# 2_MCU.net
KiCad netlist of a schematic drawn in Altium Designer
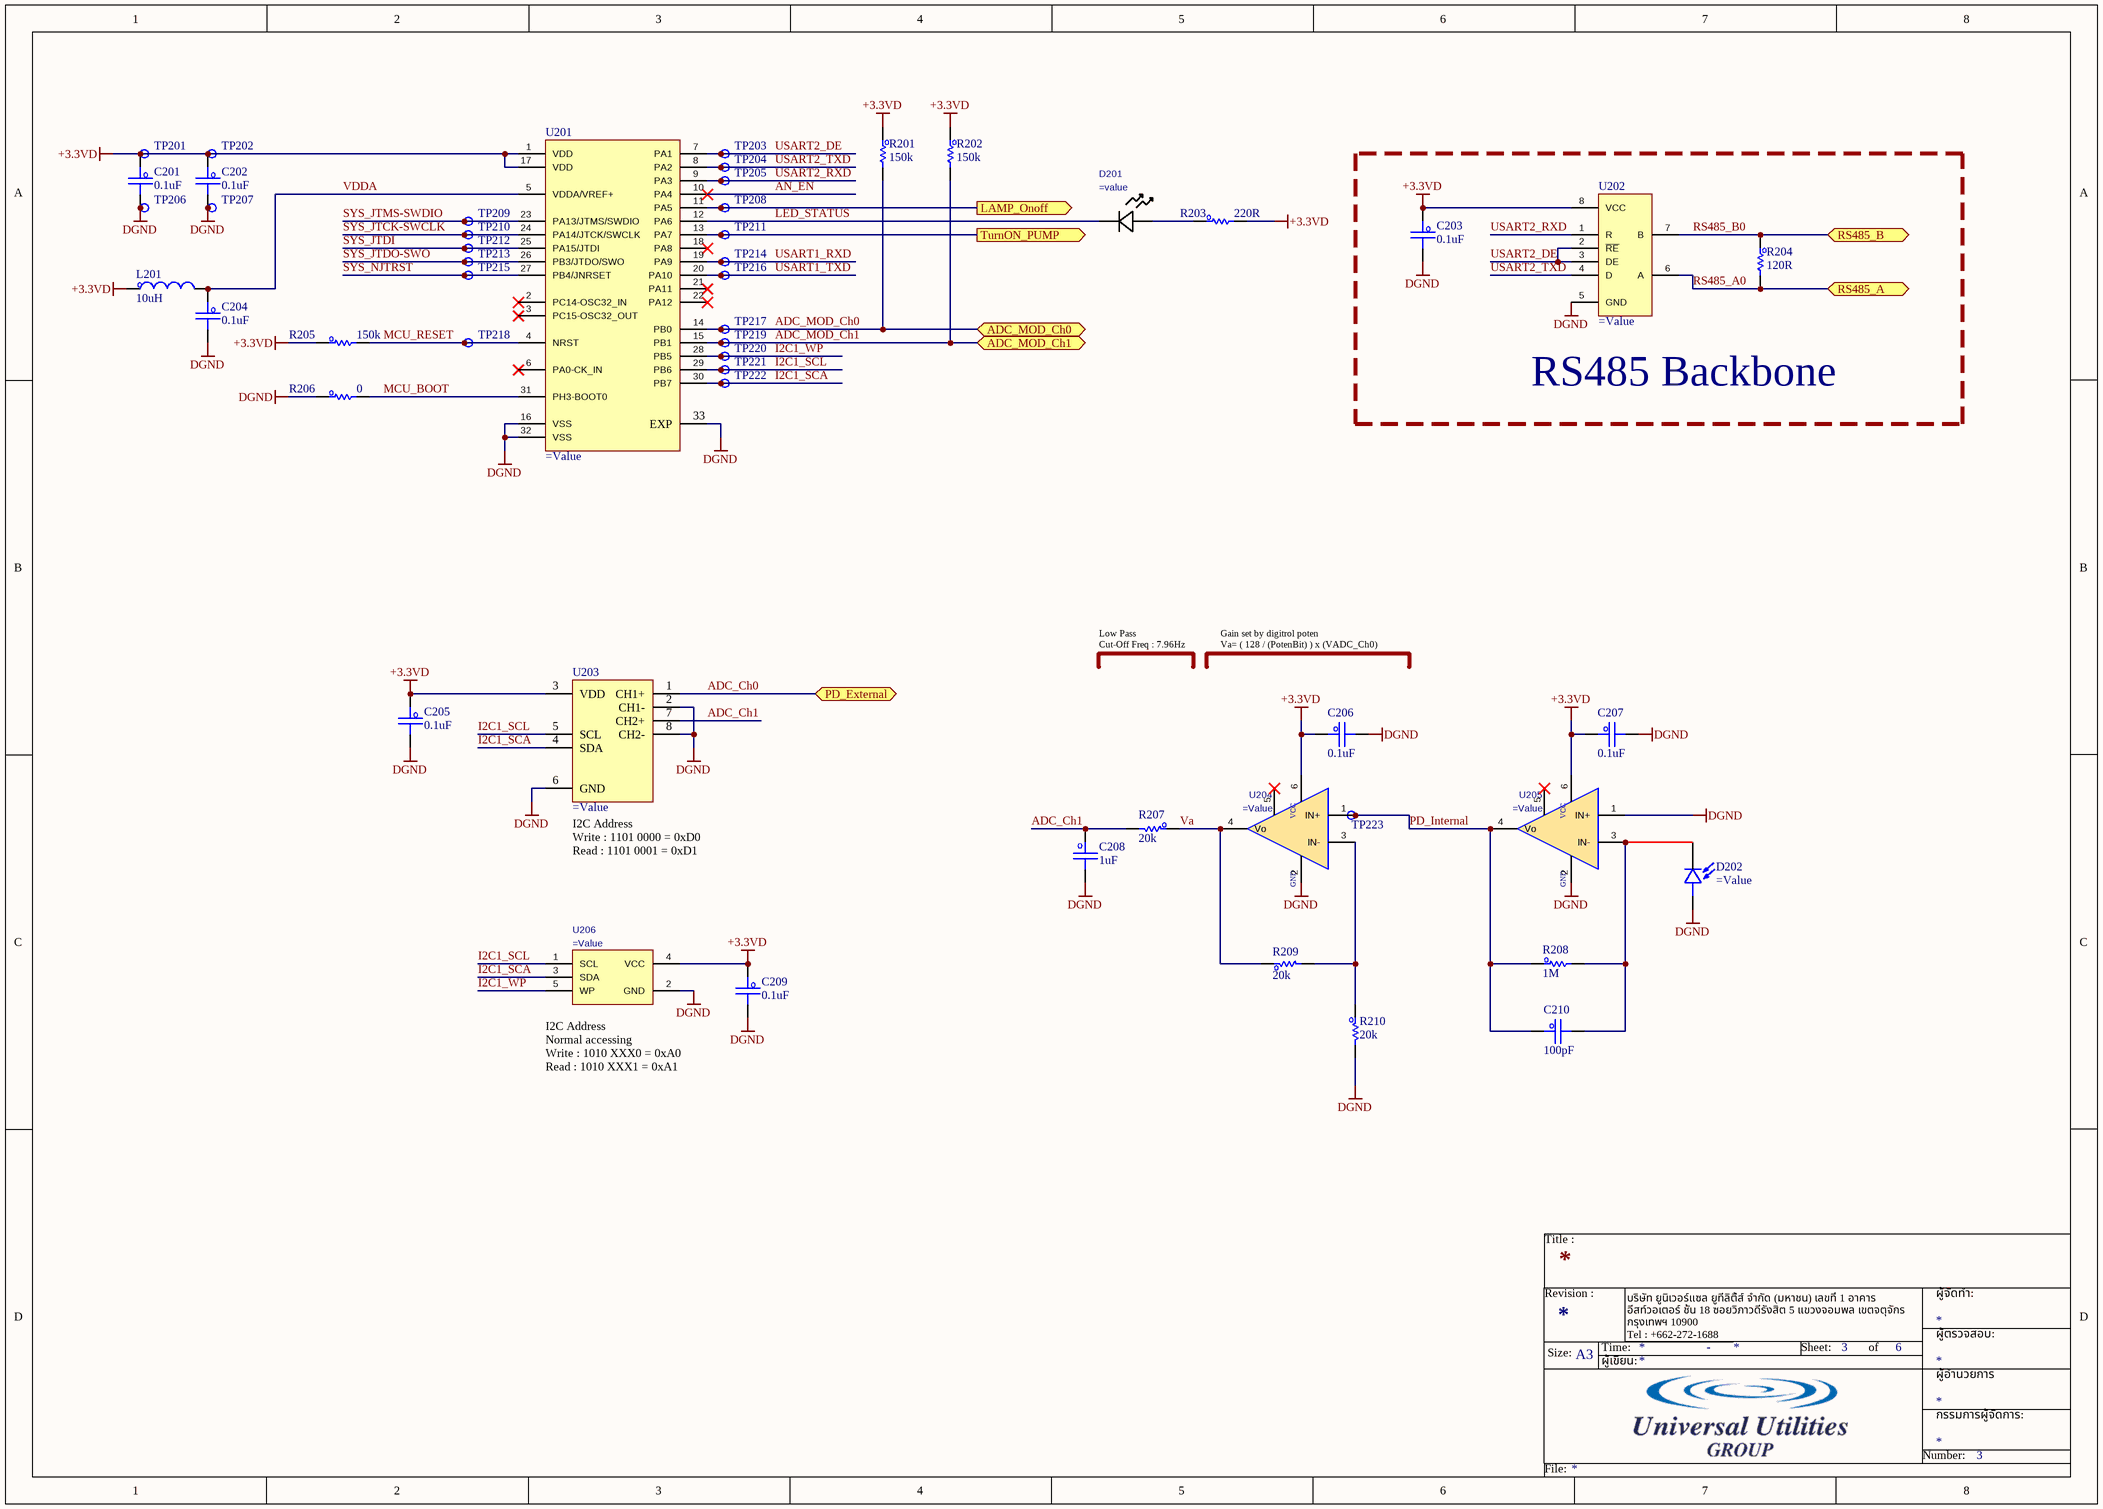
[diagram p0: 2_MCU.SchDoc]

(export (version "E")
  (design (tool "Eeschema 10.0.6"))
  (components
    (comp (ref "C201")
      (value "0.1uF")
      (footprint "C_0603")
      (description "CAP CER 0.1UF 50V X7R 0603")
      (fields (field (name "MANUFACTURER") "KEMET") (field (name "PARTNUMBER") "C0603C104K5RACTU"))
      (libsource (lib "UUSymbol") (part "C_Capacitor"))
    )
    (comp (ref "C202")
      (value "0.1uF")
      (footprint "C_0603")
      (description "CAP CER 0.1UF 50V X7R 0603")
      (fields (field (name "MANUFACTURER") "KEMET") (field (name "PARTNUMBER") "C0603C104K5RACTU"))
      (libsource (lib "UUSymbol") (part "C_Capacitor"))
    )
    (comp (ref "C203")
      (value "0.1uF")
      (footprint "C_0603")
      (description "CAP CER 0.1UF 50V X7R 0603")
      (fields (field (name "MANUFACTURER") "KEMET") (field (name "PARTNUMBER") "C0603C104K5RACTU"))
      (libsource (lib "UUSymbol") (part "C_Capacitor"))
    )
    (comp (ref "C204")
      (value "0.1uF")
      (footprint "C_0603")
      (description "CAP CER 0.1UF 50V X7R 0603")
      (fields (field (name "MANUFACTURER") "KEMET") (field (name "PARTNUMBER") "C0603C104K5RACTU"))
      (libsource (lib "UUSymbol") (part "C_Capacitor"))
    )
    (comp (ref "C205")
      (value "0.1uF")
      (footprint "C_0603")
      (description "CAP CER 0.1UF 50V X7R 0603")
      (fields (field (name "MANUFACTURER") "KEMET") (field (name "PARTNUMBER") "C0603C104K5RACTU"))
      (libsource (lib "UUSymbol") (part "C_Capacitor"))
    )
    (comp (ref "C206")
      (value "0.1uF")
      (footprint "C_0603")
      (description "CAP CER 0.1UF 50V X7R 0603")
      (fields (field (name "MANUFACTURER") "KEMET") (field (name "PARTNUMBER") "C0603C104K5RACTU"))
      (libsource (lib "UUSymbol") (part "C_Capacitor"))
    )
    (comp (ref "C207")
      (value "0.1uF")
      (footprint "C_0603")
      (description "CAP CER 0.1UF 50V X7R 0603")
      (fields (field (name "MANUFACTURER") "KEMET") (field (name "PARTNUMBER") "C0603C104K5RACTU"))
      (libsource (lib "UUSymbol") (part "C_Capacitor"))
    )
    (comp (ref "C208")
      (value "1uF")
      (footprint "C_0603")
      (description "CAP CER 0603 1UF 6.3V X7R 5%")
      (fields (field (name "MANUFACTURER") "KEMET") (field (name "PARTNUMBER") "C0603X105J9RAC7867"))
      (libsource (lib "UUSymbol") (part "C_Capacitor"))
    )
    (comp (ref "C209")
      (value "0.1uF")
      (footprint "C_0603")
      (description "CAP CER 0.1UF 50V X7R 0603")
      (fields (field (name "MANUFACTURER") "KEMET") (field (name "PARTNUMBER") "C0603C104K5RACTU"))
      (libsource (lib "UUSymbol") (part "C_Capacitor"))
    )
    (comp (ref "C210")
      (value "100pF")
      (footprint "C_0603")
      (description "CAP CER 100PF 100V X7R 0603")
      (fields (field (name "MANUFACTURER") "AVX Corporation") (field (name "PARTNUMBER") "06031C101JAT2A"))
      (libsource (lib "UUSymbol") (part "C_Capacitor"))
    )
    (comp (ref "D201")
      (value "~")
      (footprint "LED_0VS75000_WRE")
      (description "LED BLUE CLEAR 0603 SMD")
      (fields (field (name "MANUFACTURER") "Wurth Electronics") (field (name "PARTNUMBER") "150060VS75000"))
      (libsource (lib "UUSymbol") (part "D_LED_150060BS75000"))
    )
    (comp (ref "D202")
      (value "~")
      (footprint "TO254P950H570-2")
      (description "SENSOR PHOTODIODE 850NM TO39-2")
      (fields
        (field (name "PARTNUMBER") "BPX 61")
        (field (name "MANUFACTURER") "OSRAM Opto Semiconductors Inc.")
      )
      (libsource (lib "UUSymbol") (part "D_PD_BPX61"))
    )
    (comp (ref "L201")
      (value "10uH")
      (footprint "L_0402")
      (description "10µH Shielded Multilayer Inductor 250mA 1.05Ohm 0603 (1608 Metric)")
      (fields (field (name "MANUFACTURER") "TDK Corporation") (field (name "PARTNUMBER") "MLZ1608M100WT000"))
      (libsource (lib "UUSymbol") (part "L_Inductor"))
    )
    (comp (ref "R201")
      (value "150k")
      (footprint "R_0603")
      (description "RES SMD 150K OHM 1% 1/10W 0603")
      (fields (field (name "MANUFACTURER") "Vishay Dale") (field (name "PARTNUMBER") "CRCW0603150KFKEAC"))
      (libsource (lib "UUSymbol") (part "R_Resister"))
    )
    (comp (ref "R202")
      (value "150k")
      (footprint "R_0603")
      (description "RES SMD 150K OHM 1% 1/10W 0603")
      (fields (field (name "MANUFACTURER") "Vishay Dale") (field (name "PARTNUMBER") "CRCW0603150KFKEAC"))
      (libsource (lib "UUSymbol") (part "R_Resister"))
    )
    (comp (ref "R203")
      (value "220R")
      (footprint "R_0603")
      (description "RES SMD 220 OHM 1% 1/10W 0603")
      (fields (field (name "MANUFACTURER") "Vishay Dale") (field (name "PARTNUMBER") "CRCW0603220RFKEAC"))
      (libsource (lib "UUSymbol") (part "R_Resister"))
    )
    (comp (ref "R204")
      (value "120R")
      (footprint "R_0603")
      (description "RES SMD 120 OHM 1% 1/3W 0603")
      (fields (field (name "MANUFACTURER") "Vishay Dale") (field (name "PARTNUMBER") "CRCW0603120RFKEAHP"))
      (libsource (lib "UUSymbol") (part "R_Resister"))
    )
    (comp (ref "R205")
      (value "150k")
      (footprint "R_0603")
      (description "RES SMD 150K OHM 1% 1/10W 0603")
      (fields (field (name "MANUFACTURER") "Vishay Dale") (field (name "PARTNUMBER") "CRCW0603150KFKEAC"))
      (libsource (lib "UUSymbol") (part "R_Resister"))
    )
    (comp (ref "R206")
      (value "0")
      (footprint "R_0603")
      (description "RES SMD 0 OHM JUMP 1/10W 0603")
      (fields (field (name "MANUFACTURER") "Vishay Dale") (field (name "PARTNUMBER") "CRCW06030000Z0EBC"))
      (libsource (lib "UUSymbol") (part "R_Resister"))
    )
    (comp (ref "R207")
      (value "20k")
      (footprint "R_0603")
      (description "RES SMD 20K OHM 5% 1/4W 0603")
      (fields
        (field (name "MANUFACTURER") "Panasonic Electronic Components")
        (field (name "PARTNUMBER") "ERJ-PA3J203V")
      )
      (libsource (lib "UUSymbol") (part "R_Resister"))
    )
    (comp (ref "R208")
      (value "1M")
      (footprint "R_0603")
      (description "RES SMD 1M OHM 5% 1/10W 0603")
      (fields (field (name "MANUFACTURER") "YAGEO") (field (name "PARTNUMBER") "AC0603JR-071ML"))
      (libsource (lib "UUSymbol") (part "R_Resister"))
    )
    (comp (ref "R209")
      (value "20k")
      (footprint "R_0603")
      (description "RES SMD 20K OHM 5% 1/4W 0603")
      (fields
        (field (name "MANUFACTURER") "Panasonic Electronic Components")
        (field (name "PARTNUMBER") "ERJ-PA3J203V")
      )
      (libsource (lib "UUSymbol") (part "R_Resister"))
    )
    (comp (ref "R210")
      (value "20k")
      (footprint "R_0603")
      (description "RES SMD 20K OHM 5% 1/4W 0603")
      (fields
        (field (name "MANUFACTURER") "Panasonic Electronic Components")
        (field (name "PARTNUMBER") "ERJ-PA3J203V")
      )
      (libsource (lib "UUSymbol") (part "R_Resister"))
    )
    (comp (ref "TP201")
      (value "~")
      (footprint "TP_Testpoint")
      (description "TestPoint")
      (libsource (lib "UUSymbol") (part "TP_TestPoint"))
    )
    (comp (ref "TP202")
      (value "~")
      (footprint "TP_Testpoint")
      (description "TestPoint")
      (libsource (lib "UUSymbol") (part "TP_TestPoint"))
    )
    (comp (ref "TP203")
      (value "~")
      (footprint "TP_Testpoint")
      (description "TestPoint")
      (libsource (lib "UUSymbol") (part "TP_TestPoint"))
    )
    (comp (ref "TP204")
      (value "~")
      (footprint "TP_Testpoint")
      (description "TestPoint")
      (libsource (lib "UUSymbol") (part "TP_TestPoint"))
    )
    (comp (ref "TP205")
      (value "~")
      (footprint "TP_Testpoint")
      (description "TestPoint")
      (libsource (lib "UUSymbol") (part "TP_TestPoint"))
    )
    (comp (ref "TP206")
      (value "~")
      (footprint "TP_Testpoint")
      (description "TestPoint")
      (libsource (lib "UUSymbol") (part "TP_TestPoint"))
    )
    (comp (ref "TP207")
      (value "~")
      (footprint "TP_Testpoint")
      (description "TestPoint")
      (libsource (lib "UUSymbol") (part "TP_TestPoint"))
    )
    (comp (ref "TP208")
      (value "~")
      (footprint "TP_Testpoint")
      (description "TestPoint")
      (libsource (lib "UUSymbol") (part "TP_TestPoint"))
    )
    (comp (ref "TP209")
      (value "~")
      (footprint "TP_Testpoint")
      (description "TestPoint")
      (libsource (lib "UUSymbol") (part "TP_TestPoint"))
    )
    (comp (ref "TP210")
      (value "~")
      (footprint "TP_Testpoint")
      (description "TestPoint")
      (libsource (lib "UUSymbol") (part "TP_TestPoint"))
    )
    (comp (ref "TP211")
      (value "~")
      (footprint "TP_Testpoint")
      (description "TestPoint")
      (libsource (lib "UUSymbol") (part "TP_TestPoint"))
    )
    (comp (ref "TP212")
      (value "~")
      (footprint "TP_Testpoint")
      (description "TestPoint")
      (libsource (lib "UUSymbol") (part "TP_TestPoint"))
    )
    (comp (ref "TP213")
      (value "~")
      (footprint "TP_Testpoint")
      (description "TestPoint")
      (libsource (lib "UUSymbol") (part "TP_TestPoint"))
    )
    (comp (ref "TP214")
      (value "~")
      (footprint "TP_Testpoint")
      (description "TestPoint")
      (libsource (lib "UUSymbol") (part "TP_TestPoint"))
    )
    (comp (ref "TP215")
      (value "~")
      (footprint "TP_Testpoint")
      (description "TestPoint")
      (libsource (lib "UUSymbol") (part "TP_TestPoint"))
    )
    (comp (ref "TP216")
      (value "~")
      (footprint "TP_Testpoint")
      (description "TestPoint")
      (libsource (lib "UUSymbol") (part "TP_TestPoint"))
    )
    (comp (ref "TP217")
      (value "~")
      (footprint "TP_Testpoint")
      (description "TestPoint")
      (libsource (lib "UUSymbol") (part "TP_TestPoint"))
    )
    (comp (ref "TP218")
      (value "~")
      (footprint "TP_Testpoint")
      (description "TestPoint")
      (libsource (lib "UUSymbol") (part "TP_TestPoint"))
    )
    (comp (ref "TP219")
      (value "~")
      (footprint "TP_Testpoint")
      (description "TestPoint")
      (libsource (lib "UUSymbol") (part "TP_TestPoint"))
    )
    (comp (ref "TP220")
      (value "~")
      (footprint "TP_Testpoint")
      (description "TestPoint")
      (libsource (lib "UUSymbol") (part "TP_TestPoint"))
    )
    (comp (ref "TP221")
      (value "~")
      (footprint "TP_Testpoint")
      (description "TestPoint")
      (libsource (lib "UUSymbol") (part "TP_TestPoint"))
    )
    (comp (ref "TP222")
      (value "~")
      (footprint "TP_Testpoint")
      (description "TestPoint")
      (libsource (lib "UUSymbol") (part "TP_TestPoint"))
    )
    (comp (ref "TP223")
      (value "~")
      (footprint "TP_Testpoint")
      (description "TestPoint")
      (libsource (lib "UUSymbol") (part "TP_TestPoint"))
    )
    (comp (ref "U201")
      (value "~")
      (footprint "QFN50P500X500X60-33N")
      (description "IC MCU 32BIT 256KB FLSH 32UFQFPN")
      (fields (field (name "PARTNUMBER") "STM32L432KCU6") (field (name "MANUFACTURER") "STMicroelectronics"))
      (libsource (lib "UUSymbol") (part "IC_MCU_STM32L432"))
    )
    (comp (ref "U202")
      (value "~")
      (footprint "SOP65P490X110-8N")
      (description "IC TRANSCEIVER FULL 1/1 8VSSOP")
      (fields (field (name "PARTNUMBER") "SN65HVD77DGKR") (field (name "MANUFACTURER") "Texas Instruments"))
      (libsource (lib "UUSymbol") (part "IC_TRAN_SN65HVD78DGK"))
    )
    (comp (ref "U203")
      (value "~")
      (footprint "SON50P200X300X100-9N")
      (description "IC ADC 18BIT SIGMA-DELTA 8DFN")
      (fields
        (field (name "PARTNUMBER") "MCP3422A0-E/MC")
        (field (name "MANUFACTURER") "Microchip Technology")
      )
      (libsource (lib "UUSymbol") (part "IC_ADC_MCP3422A0"))
    )
    (comp (ref "U204")
      (value "~")
      (footprint "SOT65P210X110-6N")
      (description "LOW POWER, PRECISION, 50 MHZ DEC")
      (fields (field (name "MANUFACTURER") "Texas Instruments") (field (name "PARTNUMBER") "OPA607IDCKR"))
      (libsource (lib "UUSymbol") (part "IC_OPAMP_OPA607"))
    )
    (comp (ref "U205")
      (value "~")
      (footprint "SOT65P210X110-6N")
      (description "LOW POWER, PRECISION, 50 MHZ DEC")
      (fields (field (name "MANUFACTURER") "Texas Instruments") (field (name "PARTNUMBER") "OPA607IDCKR"))
      (libsource (lib "UUSymbol") (part "IC_OPAMP_OPA607"))
    )
    (comp (ref "U206")
      (value "~")
      (footprint "SOT65P210X110-5N")
      (description "IC EEPROM 2KBIT I2C SC70-5")
      (fields
        (field (name "MANUFACTURER") "Microchip Technology")
        (field (name "PARTNUMBER") "24AA02HT-I/LT")
      )
      (libsource (lib "UUSymbol") (part "IC_MEM_24AA02HT"))
    )
  )
  (nets
    (net (code "1") (name "+3.3VD") (class "Default")
      (node (ref "C201") (pin "1") (pinfunction "1_1") (pintype "passive"))
      (node (ref "C202") (pin "1") (pinfunction "1_1") (pintype "passive"))
      (node (ref "C203") (pin "1") (pinfunction "1_1") (pintype "passive"))
      (node (ref "C205") (pin "1") (pinfunction "1_1") (pintype "passive"))
      (node (ref "C206") (pin "1") (pinfunction "1_1") (pintype "passive"))
      (node (ref "C207") (pin "1") (pinfunction "1_1") (pintype "passive"))
      (node (ref "C209") (pin "1") (pinfunction "1_1") (pintype "passive"))
      (node (ref "L201") (pin "1") (pinfunction "1_1") (pintype "passive"))
      (node (ref "R201") (pin "1") (pinfunction "1_1") (pintype "passive"))
      (node (ref "R202") (pin "1") (pinfunction "1_1") (pintype "passive"))
      (node (ref "R203") (pin "2") (pinfunction "2_2") (pintype "passive"))
      (node (ref "R205") (pin "1") (pinfunction "1_1") (pintype "passive"))
      (node (ref "TP201") (pin "1") (pinfunction "1_1") (pintype "passive"))
      (node (ref "TP202") (pin "1") (pinfunction "1_1") (pintype "passive"))
      (node (ref "U201") (pin "1") (pinfunction "VDD_1") (pintype "passive"))
      (node (ref "U201") (pin "17") (pinfunction "VDD_17") (pintype "passive"))
      (node (ref "U202") (pin "8") (pinfunction "VCC_8") (pintype "passive"))
      (node (ref "U203") (pin "3") (pinfunction "VDD_3") (pintype "passive"))
      (node (ref "U204") (pin "6") (pinfunction "VDD_6") (pintype "passive"))
      (node (ref "U205") (pin "6") (pinfunction "VDD_6") (pintype "passive"))
      (node (ref "U206") (pin "4") (pinfunction "VCC_4") (pintype "passive"))
    )
    (net (code "2") (name "/ADC_Ch0") (class "Default")
      (node (ref "U203") (pin "1") (pinfunction "CH1+_1") (pintype "passive"))
    )
    (net (code "3") (name "/ADC_Ch1") (class "Default")
      (node (ref "C208") (pin "1") (pinfunction "1_1") (pintype "passive"))
      (node (ref "R207") (pin "2") (pinfunction "2_2") (pintype "passive"))
      (node (ref "U203") (pin "7") (pinfunction "CH2+_7") (pintype "passive"))
    )
    (net (code "4") (name "/ADC_MOD_Ch0") (class "Default")
      (node (ref "R201") (pin "2") (pinfunction "2_2") (pintype "passive"))
      (node (ref "TP217") (pin "1") (pinfunction "1_1") (pintype "passive"))
      (node (ref "U201") (pin "14") (pinfunction "PB0_14") (pintype "passive"))
    )
    (net (code "5") (name "/ADC_MOD_Ch1") (class "Default")
      (node (ref "R202") (pin "2") (pinfunction "2_2") (pintype "passive"))
      (node (ref "TP219") (pin "1") (pinfunction "1_1") (pintype "passive"))
      (node (ref "U201") (pin "15") (pinfunction "PB1_15") (pintype "passive"))
    )
    (net (code "6") (name "/AN_EN") (class "Default")
      (node (ref "U201") (pin "10") (pinfunction "PA4_10") (pintype "passive+no_connect"))
    )
    (net (code "7") (name "/I2C1_SCA") (class "Default")
      (node (ref "TP222") (pin "1") (pinfunction "1_1") (pintype "passive"))
      (node (ref "U201") (pin "30") (pinfunction "PB7_30") (pintype "passive"))
      (node (ref "U203") (pin "4") (pinfunction "SDA_4") (pintype "passive"))
      (node (ref "U206") (pin "3") (pinfunction "SDA_3") (pintype "passive"))
    )
    (net (code "8") (name "/I2C1_SCL") (class "Default")
      (node (ref "TP221") (pin "1") (pinfunction "1_1") (pintype "passive"))
      (node (ref "U201") (pin "29") (pinfunction "PB6_29") (pintype "passive"))
      (node (ref "U203") (pin "5") (pinfunction "SCL_5") (pintype "passive"))
      (node (ref "U206") (pin "1") (pinfunction "SCL_1") (pintype "passive"))
    )
    (net (code "9") (name "/I2C1_WP") (class "Default")
      (node (ref "TP220") (pin "1") (pinfunction "1_1") (pintype "passive"))
      (node (ref "U201") (pin "28") (pinfunction "PB5_28") (pintype "passive"))
      (node (ref "U206") (pin "5") (pinfunction "WP_5") (pintype "passive"))
    )
    (net (code "10") (name "/LAMP_Onoff") (class "Default")
      (node (ref "TP208") (pin "1") (pinfunction "1_1") (pintype "passive"))
      (node (ref "U201") (pin "11") (pinfunction "PA5_11") (pintype "passive"))
    )
    (net (code "11") (name "/LED_STATUS") (class "Default")
      (node (ref "D201") (pin "2") (pinfunction "2_2") (pintype "passive"))
      (node (ref "U201") (pin "12") (pinfunction "PA6_12") (pintype "passive"))
    )
    (net (code "12") (name "/MCU_BOOT") (class "Default")
      (node (ref "R206") (pin "2") (pinfunction "2_2") (pintype "passive"))
      (node (ref "U201") (pin "31") (pinfunction "PH3-BOOT0_31") (pintype "passive"))
    )
    (net (code "13") (name "/MCU_RESET") (class "Default")
      (node (ref "R205") (pin "2") (pinfunction "2_2") (pintype "passive"))
      (node (ref "TP218") (pin "1") (pinfunction "1_1") (pintype "passive"))
      (node (ref "U201") (pin "4") (pinfunction "NRST_4") (pintype "passive"))
    )
    (net (code "14") (name "/PD_Internal") (class "Default")
      (node (ref "C210") (pin "1") (pinfunction "1_1") (pintype "passive"))
      (node (ref "R208") (pin "1") (pinfunction "1_1") (pintype "passive"))
      (node (ref "TP223") (pin "1") (pinfunction "1_1") (pintype "passive"))
      (node (ref "U204") (pin "1") (pinfunction "IN+_1") (pintype "passive"))
      (node (ref "U205") (pin "4") (pinfunction "Vo_4") (pintype "passive"))
    )
    (net (code "15") (name "/RS485_A0") (class "Default")
      (node (ref "R204") (pin "2") (pinfunction "2_2") (pintype "passive"))
      (node (ref "U202") (pin "6") (pinfunction "A_6") (pintype "passive"))
    )
    (net (code "16") (name "/RS485_B0") (class "Default")
      (node (ref "R204") (pin "1") (pinfunction "1_1") (pintype "passive"))
      (node (ref "U202") (pin "7") (pinfunction "B_7") (pintype "passive"))
    )
    (net (code "17") (name "/SYS_JTCK-SWCLK") (class "Default")
      (node (ref "TP210") (pin "1") (pinfunction "1_1") (pintype "passive"))
      (node (ref "U201") (pin "24") (pinfunction "PA14/JTCK/SWCLK_24") (pintype "passive"))
    )
    (net (code "18") (name "/SYS_JTDI") (class "Default")
      (node (ref "TP212") (pin "1") (pinfunction "1_1") (pintype "passive"))
      (node (ref "U201") (pin "25") (pinfunction "PA15/JTDI_25") (pintype "passive"))
    )
    (net (code "19") (name "/SYS_JTDO-SWO") (class "Default")
      (node (ref "TP213") (pin "1") (pinfunction "1_1") (pintype "passive"))
      (node (ref "U201") (pin "26") (pinfunction "PB3/JTDO/SWO_26") (pintype "passive"))
    )
    (net (code "20") (name "/SYS_JTMS-SWDIO") (class "Default")
      (node (ref "TP209") (pin "1") (pinfunction "1_1") (pintype "passive"))
      (node (ref "U201") (pin "23") (pinfunction "PA13/JTMS/SWDIO_23") (pintype "passive"))
    )
    (net (code "21") (name "/SYS_NJTRST") (class "Default")
      (node (ref "TP215") (pin "1") (pinfunction "1_1") (pintype "passive"))
      (node (ref "U201") (pin "27") (pinfunction "PB4/JNRSET_27") (pintype "passive"))
    )
    (net (code "22") (name "/TurnON_PUMP") (class "Default")
      (node (ref "TP211") (pin "1") (pinfunction "1_1") (pintype "passive"))
      (node (ref "U201") (pin "13") (pinfunction "PA7_13") (pintype "passive"))
    )
    (net (code "23") (name "/USART1_RXD") (class "Default")
      (node (ref "TP214") (pin "1") (pinfunction "1_1") (pintype "passive"))
      (node (ref "U201") (pin "19") (pinfunction "PA9_19") (pintype "passive"))
    )
    (net (code "24") (name "/USART1_TXD") (class "Default")
      (node (ref "TP216") (pin "1") (pinfunction "1_1") (pintype "passive"))
      (node (ref "U201") (pin "20") (pinfunction "PA10_20") (pintype "passive"))
    )
    (net (code "25") (name "/USART2_DE") (class "Default")
      (node (ref "TP203") (pin "1") (pinfunction "1_1") (pintype "passive"))
      (node (ref "U201") (pin "7") (pinfunction "PA1_7") (pintype "passive"))
      (node (ref "U202") (pin "2") (pinfunction "~{RE}_2") (pintype "passive"))
      (node (ref "U202") (pin "3") (pinfunction "DE_3") (pintype "passive"))
    )
    (net (code "26") (name "/USART2_RXD") (class "Default")
      (node (ref "TP205") (pin "1") (pinfunction "1_1") (pintype "passive"))
      (node (ref "U201") (pin "9") (pinfunction "PA3_9") (pintype "passive"))
      (node (ref "U202") (pin "1") (pinfunction "R_1") (pintype "passive"))
    )
    (net (code "27") (name "/USART2_TXD") (class "Default")
      (node (ref "TP204") (pin "1") (pinfunction "1_1") (pintype "passive"))
      (node (ref "U201") (pin "8") (pinfunction "PA2_8") (pintype "passive"))
      (node (ref "U202") (pin "4") (pinfunction "D_4") (pintype "passive"))
    )
    (net (code "28") (name "/VDDA") (class "Default")
      (node (ref "C204") (pin "1") (pinfunction "1_1") (pintype "passive"))
      (node (ref "L201") (pin "2") (pinfunction "2_2") (pintype "passive"))
      (node (ref "U201") (pin "5") (pinfunction "VDDA/VREF+_5") (pintype "passive"))
    )
    (net (code "29") (name "/Va") (class "Default")
      (node (ref "R207") (pin "1") (pinfunction "1_1") (pintype "passive"))
      (node (ref "R209") (pin "1") (pinfunction "1_1") (pintype "passive"))
      (node (ref "U204") (pin "4") (pinfunction "Vo_4") (pintype "passive"))
    )
    (net (code "30") (name "DGND") (class "Default")
      (node (ref "C201") (pin "2") (pinfunction "2_2") (pintype "passive"))
      (node (ref "C202") (pin "2") (pinfunction "2_2") (pintype "passive"))
      (node (ref "C203") (pin "2") (pinfunction "2_2") (pintype "passive"))
      (node (ref "C204") (pin "2") (pinfunction "2_2") (pintype "passive"))
      (node (ref "C205") (pin "2") (pinfunction "2_2") (pintype "passive"))
      (node (ref "C206") (pin "2") (pinfunction "2_2") (pintype "passive"))
      (node (ref "C207") (pin "2") (pinfunction "2_2") (pintype "passive"))
      (node (ref "C208") (pin "2") (pinfunction "2_2") (pintype "passive"))
      (node (ref "C209") (pin "2") (pinfunction "2_2") (pintype "passive"))
      (node (ref "D202") (pin "A") (pinfunction "A_A") (pintype "passive"))
      (node (ref "R206") (pin "1") (pinfunction "1_1") (pintype "passive"))
      (node (ref "R210") (pin "2") (pinfunction "2_2") (pintype "passive"))
      (node (ref "TP206") (pin "1") (pinfunction "1_1") (pintype "passive"))
      (node (ref "TP207") (pin "1") (pinfunction "1_1") (pintype "passive"))
      (node (ref "U201") (pin "16") (pinfunction "VSS_16") (pintype "passive"))
      (node (ref "U201") (pin "32") (pinfunction "VSS_32") (pintype "passive"))
      (node (ref "U201") (pin "33") (pinfunction "EXP_33") (pintype "passive"))
      (node (ref "U202") (pin "5") (pinfunction "GND_5") (pintype "passive"))
      (node (ref "U203") (pin "2") (pinfunction "CH1-_2") (pintype "passive"))
      (node (ref "U203") (pin "6") (pinfunction "GND_6") (pintype "passive"))
      (node (ref "U203") (pin "8") (pinfunction "CH2-_8") (pintype "passive"))
      (node (ref "U204") (pin "2") (pinfunction "GND_2") (pintype "passive"))
      (node (ref "U205") (pin "1") (pinfunction "IN+_1") (pintype "passive"))
      (node (ref "U205") (pin "2") (pinfunction "GND_2") (pintype "passive"))
      (node (ref "U206") (pin "2") (pinfunction "GND_2") (pintype "passive"))
    )
    (net (code "31") (name "Net-(D201-Pad1)") (class "Default")
      (node (ref "D201") (pin "1") (pinfunction "1_1") (pintype "passive"))
      (node (ref "R203") (pin "1") (pinfunction "1_1") (pintype "passive"))
    )
    (net (code "32") (name "Net-(U204-IN-)") (class "Default")
      (node (ref "R209") (pin "2") (pinfunction "2_2") (pintype "passive"))
      (node (ref "R210") (pin "1") (pinfunction "1_1") (pintype "passive"))
      (node (ref "U204") (pin "3") (pinfunction "IN-_3") (pintype "passive"))
    )
    (net (code "33") (name "Net-(U205-IN-)") (class "Default")
      (node (ref "C210") (pin "2") (pinfunction "2_2") (pintype "passive"))
      (node (ref "D202") (pin "C") (pinfunction "C_C") (pintype "passive"))
      (node (ref "R208") (pin "2") (pinfunction "2_2") (pintype "passive"))
      (node (ref "U205") (pin "3") (pinfunction "IN-_3") (pintype "passive"))
    )
    (net (code "34") (name "unconnected-(U201-PA0-CK_IN-Pad6)") (class "Default")
      (node (ref "U201") (pin "6") (pinfunction "PA0-CK_IN_6") (pintype "passive+no_connect"))
    )
    (net (code "35") (name "unconnected-(U201-PA8-Pad18)") (class "Default")
      (node (ref "U201") (pin "18") (pinfunction "PA8_18") (pintype "passive+no_connect"))
    )
    (net (code "36") (name "unconnected-(U201-PA11-Pad21)") (class "Default")
      (node (ref "U201") (pin "21") (pinfunction "PA11_21") (pintype "passive+no_connect"))
    )
    (net (code "37") (name "unconnected-(U201-PA12-Pad22)") (class "Default")
      (node (ref "U201") (pin "22") (pinfunction "PA12_22") (pintype "passive+no_connect"))
    )
    (net (code "38") (name "unconnected-(U201-PC14-OSC32_IN-Pad2)") (class "Default")
      (node (ref "U201") (pin "2") (pinfunction "PC14-OSC32_IN_2") (pintype "passive+no_connect"))
    )
    (net (code "39") (name "unconnected-(U201-PC15-OSC32_OUT-Pad3)") (class "Default")
      (node (ref "U201") (pin "3") (pinfunction "PC15-OSC32_OUT_3") (pintype "passive+no_connect"))
    )
    (net (code "40") (name "unconnected-(U204-Vo-Pad5)") (class "Default")
      (node (ref "U204") (pin "5") (pinfunction "Vo_5") (pintype "passive+no_connect"))
    )
    (net (code "41") (name "unconnected-(U205-Vo-Pad5)") (class "Default")
      (node (ref "U205") (pin "5") (pinfunction "Vo_5") (pintype "passive+no_connect"))
    )
  )
)
